# Power.net
KiCad netlist of a schematic drawn in Altium Designer
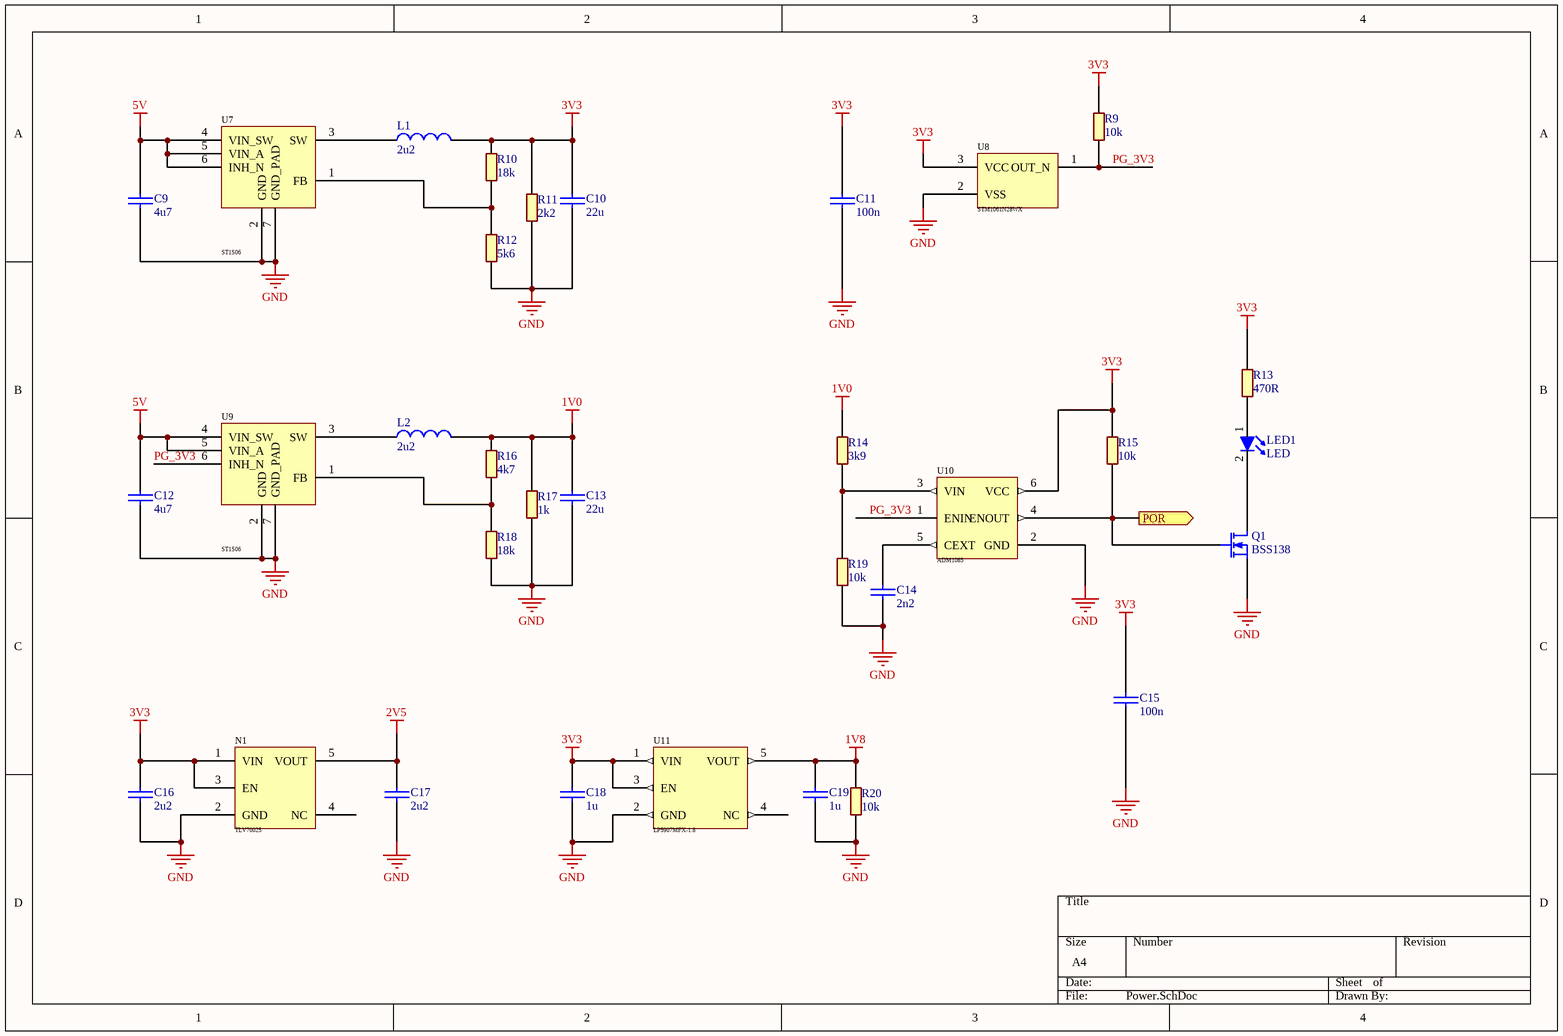
[diagram p0: Power.SchDoc]

(export (version "E")
  (design (tool "Eeschema 10.0.6"))
  (components
    (comp (ref "C9")
      (value "4u7")
      (footprint "C0805")
      (description "Capacitor")
      (libsource (lib "Library") (part "CAP"))
    )
    (comp (ref "C10")
      (value "22u")
      (footprint "C1206")
      (description "Capacitor")
      (libsource (lib "Library") (part "CAP"))
    )
    (comp (ref "C11")
      (value "100n")
      (footprint "C0603")
      (description "Capacitor")
      (libsource (lib "Library") (part "CAP"))
    )
    (comp (ref "C12")
      (value "4u7")
      (footprint "C0805")
      (description "Capacitor")
      (libsource (lib "Library") (part "CAP"))
    )
    (comp (ref "C13")
      (value "22u")
      (footprint "C1206")
      (description "Capacitor")
      (libsource (lib "Library") (part "CAP"))
    )
    (comp (ref "C14")
      (value "2n2")
      (footprint "C0603")
      (description "Capacitor")
      (libsource (lib "Library") (part "CAP"))
    )
    (comp (ref "C15")
      (value "100n")
      (footprint "C0603")
      (description "Capacitor")
      (libsource (lib "Library") (part "CAP"))
    )
    (comp (ref "C16")
      (value "2u2")
      (footprint "C0805")
      (description "Capacitor")
      (libsource (lib "Library") (part "CAP"))
    )
    (comp (ref "C17")
      (value "2u2")
      (footprint "C0805")
      (description "Capacitor")
      (libsource (lib "Library") (part "CAP"))
    )
    (comp (ref "C18")
      (value "1u")
      (footprint "C0603")
      (description "Capacitor")
      (libsource (lib "Library") (part "CAP"))
    )
    (comp (ref "C19")
      (value "1u")
      (footprint "C0603")
      (description "Capacitor")
      (libsource (lib "Library") (part "CAP"))
    )
    (comp (ref "L1")
      (value "2u2")
      (footprint "L5.8X3.4")
      (description "Inductor")
      (libsource (lib "Library") (part "L"))
    )
    (comp (ref "L2")
      (value "2u2")
      (footprint "L5.8X3.4")
      (description "Inductor")
      (libsource (lib "Library") (part "L"))
    )
    (comp (ref "LED1") (value "LED") (footprint "LED0603") (libsource (lib "Library") (part "LED")))
    (comp (ref "N1") (value "TLV70025") (footprint "SOT-23-5") (libsource (lib "Library") (part "TLV70025")))
    (comp (ref "Q1")
      (value "BSS138")
      (footprint "SOT-23")
      (description "N-Channel MOSFET")
      (fields (field (name "PUBLISHER") "Altium Limited"))
      (libsource (lib "Miscellaneous Devices") (part "MOSFET-N"))
    )
    (comp (ref "R9")
      (value "10k")
      (footprint "R0603")
      (description "RES")
      (libsource (lib "Library") (part "R"))
    )
    (comp (ref "R10")
      (value "18k")
      (footprint "R0603")
      (description "RES")
      (libsource (lib "Library") (part "R"))
    )
    (comp (ref "R11")
      (value "2k2")
      (footprint "R0603")
      (description "RES")
      (libsource (lib "Library") (part "R"))
    )
    (comp (ref "R12") (value "5k6") (footprint "R0603") (description "RES") (libsource (lib "") (part "R_1")))
    (comp (ref "R13")
      (value "470R")
      (footprint "R0603")
      (description "RES")
      (libsource (lib "Library") (part "R"))
    )
    (comp (ref "R14")
      (value "3k9")
      (footprint "R0603")
      (description "RES")
      (libsource (lib "Library") (part "R"))
    )
    (comp (ref "R15")
      (value "10k")
      (footprint "R0603")
      (description "RES")
      (libsource (lib "Library") (part "R"))
    )
    (comp (ref "R16")
      (value "4k7")
      (footprint "R0603")
      (description "RES")
      (libsource (lib "Library") (part "R"))
    )
    (comp (ref "R17")
      (value "1k")
      (footprint "R0603")
      (description "RES")
      (libsource (lib "Library") (part "R"))
    )
    (comp (ref "R18") (value "18k") (footprint "R0603") (description "RES") (libsource (lib "") (part "R_1")))
    (comp (ref "R19")
      (value "10k")
      (footprint "R0603")
      (description "RES")
      (libsource (lib "Library") (part "R"))
    )
    (comp (ref "R20")
      (value "10k")
      (footprint "R0603")
      (description "RES")
      (libsource (lib "Library") (part "R"))
    )
    (comp (ref "U7") (value "ST1S06") (libsource (lib "Library") (part "ST1S06")))
    (comp (ref "U8")
      (value "STM1061N28WX")
      (footprint "SOT-23")
      (libsource (lib "Library") (part "STM1061N28WX"))
    )
    (comp (ref "U9") (value "ST1S06") (libsource (lib "Library") (part "ST1S06")))
    (comp (ref "U10") (value "ADM1085") (footprint "SC70-6") (libsource (lib "Library") (part "ADM1085")))
    (comp (ref "U11")
      (value "LP5907MFX-1.8")
      (footprint "LC-SOT-23-5")
      (libsource (lib "Library") (part "LP5907MFX-1.8"))
    )
  )
  (nets
    (net (code "1") (name "/PG_3V3") (class "Default")
      (node (ref "R9") (pin "2") (pinfunction "2_2") (pintype "passive"))
      (node (ref "U10") (pin "1") (pinfunction "ENIN_1") (pintype "passive"))
      (node (ref "U8") (pin "1") (pinfunction "OUT_N_1") (pintype "power_in"))
      (node (ref "U9") (pin "6") (pinfunction "INH_N_6") (pintype "power_in"))
    )
    (net (code "2") (name "/POR") (class "Default")
      (node (ref "Q1") (pin "2") (pinfunction "G_2") (pintype "passive"))
      (node (ref "R15") (pin "2") (pinfunction "2_2") (pintype "passive"))
      (node (ref "U10") (pin "4") (pinfunction "ENOUT_4") (pintype "output"))
    )
    (net (code "3") (name "1V0") (class "Default")
      (node (ref "C13") (pin "1") (pinfunction "1_1") (pintype "passive"))
      (node (ref "L2") (pin "2") (pinfunction "2_2") (pintype "passive"))
      (node (ref "R14") (pin "1") (pinfunction "1_1") (pintype "passive"))
      (node (ref "R16") (pin "1") (pinfunction "1_1") (pintype "passive"))
      (node (ref "R17") (pin "1") (pinfunction "1_1") (pintype "passive"))
    )
    (net (code "4") (name "1V8") (class "Default")
      (node (ref "C19") (pin "1") (pinfunction "1_1") (pintype "passive"))
      (node (ref "R20") (pin "1") (pinfunction "1_1") (pintype "passive"))
      (node (ref "U11") (pin "5") (pinfunction "VOUT_5") (pintype "output"))
    )
    (net (code "5") (name "2V5") (class "Default")
      (node (ref "C17") (pin "1") (pinfunction "1_1") (pintype "passive"))
      (node (ref "N1") (pin "5") (pinfunction "VOUT_5") (pintype "passive"))
    )
    (net (code "6") (name "3V3") (class "Default")
      (node (ref "C10") (pin "1") (pinfunction "1_1") (pintype "passive"))
      (node (ref "C11") (pin "1") (pinfunction "1_1") (pintype "passive"))
      (node (ref "C15") (pin "1") (pinfunction "1_1") (pintype "passive"))
      (node (ref "C16") (pin "1") (pinfunction "1_1") (pintype "passive"))
      (node (ref "C18") (pin "1") (pinfunction "1_1") (pintype "passive"))
      (node (ref "L1") (pin "2") (pinfunction "2_2") (pintype "passive"))
      (node (ref "N1") (pin "1") (pinfunction "VIN_1") (pintype "passive"))
      (node (ref "N1") (pin "3") (pinfunction "EN_3") (pintype "passive"))
      (node (ref "R10") (pin "1") (pinfunction "1_1") (pintype "passive"))
      (node (ref "R11") (pin "1") (pinfunction "1_1") (pintype "passive"))
      (node (ref "R13") (pin "1") (pinfunction "1_1") (pintype "passive"))
      (node (ref "R15") (pin "1") (pinfunction "1_1") (pintype "passive"))
      (node (ref "R9") (pin "1") (pinfunction "1_1") (pintype "passive"))
      (node (ref "U10") (pin "6") (pinfunction "VCC_6") (pintype "output"))
      (node (ref "U11") (pin "1") (pinfunction "VIN_1") (pintype "output"))
      (node (ref "U11") (pin "3") (pinfunction "EN_3") (pintype "output"))
      (node (ref "U8") (pin "3") (pinfunction "VCC_3") (pintype "power_in"))
    )
    (net (code "7") (name "5V") (class "Default")
      (node (ref "C12") (pin "1") (pinfunction "1_1") (pintype "passive"))
      (node (ref "C9") (pin "1") (pinfunction "1_1") (pintype "passive"))
      (node (ref "U7") (pin "4") (pinfunction "VIN_SW_4") (pintype "power_in"))
      (node (ref "U7") (pin "5") (pinfunction "VIN_A_5") (pintype "power_in"))
      (node (ref "U7") (pin "6") (pinfunction "INH_N_6") (pintype "power_in"))
      (node (ref "U9") (pin "4") (pinfunction "VIN_SW_4") (pintype "power_in"))
      (node (ref "U9") (pin "5") (pinfunction "VIN_A_5") (pintype "power_in"))
    )
    (net (code "8") (name "GND") (class "Default")
      (node (ref "C10") (pin "2") (pinfunction "2_2") (pintype "passive"))
      (node (ref "C11") (pin "2") (pinfunction "2_2") (pintype "passive"))
      (node (ref "C12") (pin "2") (pinfunction "2_2") (pintype "passive"))
      (node (ref "C13") (pin "2") (pinfunction "2_2") (pintype "passive"))
      (node (ref "C14") (pin "2") (pinfunction "2_2") (pintype "passive"))
      (node (ref "C15") (pin "2") (pinfunction "2_2") (pintype "passive"))
      (node (ref "C16") (pin "2") (pinfunction "2_2") (pintype "passive"))
      (node (ref "C17") (pin "2") (pinfunction "2_2") (pintype "passive"))
      (node (ref "C18") (pin "2") (pinfunction "2_2") (pintype "passive"))
      (node (ref "C19") (pin "2") (pinfunction "2_2") (pintype "passive"))
      (node (ref "C9") (pin "2") (pinfunction "2_2") (pintype "passive"))
      (node (ref "N1") (pin "2") (pinfunction "GND_2") (pintype "passive"))
      (node (ref "Q1") (pin "3") (pinfunction "S_3") (pintype "passive"))
      (node (ref "R11") (pin "2") (pinfunction "2_2") (pintype "passive"))
      (node (ref "R12") (pin "1") (pinfunction "1_1") (pintype "passive"))
      (node (ref "R17") (pin "2") (pinfunction "2_2") (pintype "passive"))
      (node (ref "R18") (pin "1") (pinfunction "1_1") (pintype "passive"))
      (node (ref "R19") (pin "2") (pinfunction "2_2") (pintype "passive"))
      (node (ref "R20") (pin "2") (pinfunction "2_2") (pintype "passive"))
      (node (ref "U10") (pin "2") (pinfunction "GND_2") (pintype "passive"))
      (node (ref "U11") (pin "2") (pinfunction "GND_2") (pintype "output"))
      (node (ref "U7") (pin "2") (pinfunction "GND_2") (pintype "power_in"))
      (node (ref "U7") (pin "7") (pinfunction "GND_PAD_7") (pintype "power_in"))
      (node (ref "U8") (pin "2") (pinfunction "VSS_2") (pintype "power_in"))
      (node (ref "U9") (pin "2") (pinfunction "GND_2") (pintype "power_in"))
      (node (ref "U9") (pin "7") (pinfunction "GND_PAD_7") (pintype "power_in"))
    )
    (net (code "9") (name "Net-(LED1-Pad1)") (class "Default")
      (node (ref "LED1") (pin "1") (pinfunction "1_1") (pintype "passive"))
      (node (ref "R13") (pin "2") (pinfunction "2_2") (pintype "passive"))
    )
    (net (code "10") (name "Net-(Q1-D)") (class "Default")
      (node (ref "LED1") (pin "2") (pinfunction "2_2") (pintype "passive"))
      (node (ref "Q1") (pin "1") (pinfunction "D_1") (pintype "passive"))
    )
    (net (code "11") (name "Net-(U7-FB)") (class "Default")
      (node (ref "R10") (pin "2") (pinfunction "2_2") (pintype "passive"))
      (node (ref "R12") (pin "2") (pinfunction "2_2") (pintype "passive"))
      (node (ref "U7") (pin "1") (pinfunction "FB_1") (pintype "power_in"))
    )
    (net (code "12") (name "Net-(U7-SW)") (class "Default")
      (node (ref "L1") (pin "1") (pinfunction "1_1") (pintype "passive"))
      (node (ref "U7") (pin "3") (pinfunction "SW_3") (pintype "power_in"))
    )
    (net (code "13") (name "Net-(U9-FB)") (class "Default")
      (node (ref "R16") (pin "2") (pinfunction "2_2") (pintype "passive"))
      (node (ref "R18") (pin "2") (pinfunction "2_2") (pintype "passive"))
      (node (ref "U9") (pin "1") (pinfunction "FB_1") (pintype "power_in"))
    )
    (net (code "14") (name "Net-(U9-SW)") (class "Default")
      (node (ref "L2") (pin "1") (pinfunction "1_1") (pintype "passive"))
      (node (ref "U9") (pin "3") (pinfunction "SW_3") (pintype "power_in"))
    )
    (net (code "15") (name "Net-(U10-CEXT)") (class "Default")
      (node (ref "C14") (pin "1") (pinfunction "1_1") (pintype "passive"))
      (node (ref "U10") (pin "5") (pinfunction "CEXT_5") (pintype "output"))
    )
    (net (code "16") (name "Net-(U10-VIN)") (class "Default")
      (node (ref "R14") (pin "2") (pinfunction "2_2") (pintype "passive"))
      (node (ref "R19") (pin "1") (pinfunction "1_1") (pintype "passive"))
      (node (ref "U10") (pin "3") (pinfunction "VIN_3") (pintype "output"))
    )
    (net (code "17") (name "unconnected-(N1-NC-Pad4)") (class "Default")
      (node (ref "N1") (pin "4") (pinfunction "NC_4") (pintype "passive"))
    )
    (net (code "18") (name "unconnected-(U11-NC-Pad4)") (class "Default")
      (node (ref "U11") (pin "4") (pinfunction "NC_4") (pintype "output"))
    )
  )
)
